# BreadBoard-Power-Supply_v10.net
KiCad netlist of a schematic drawn in EAGLE
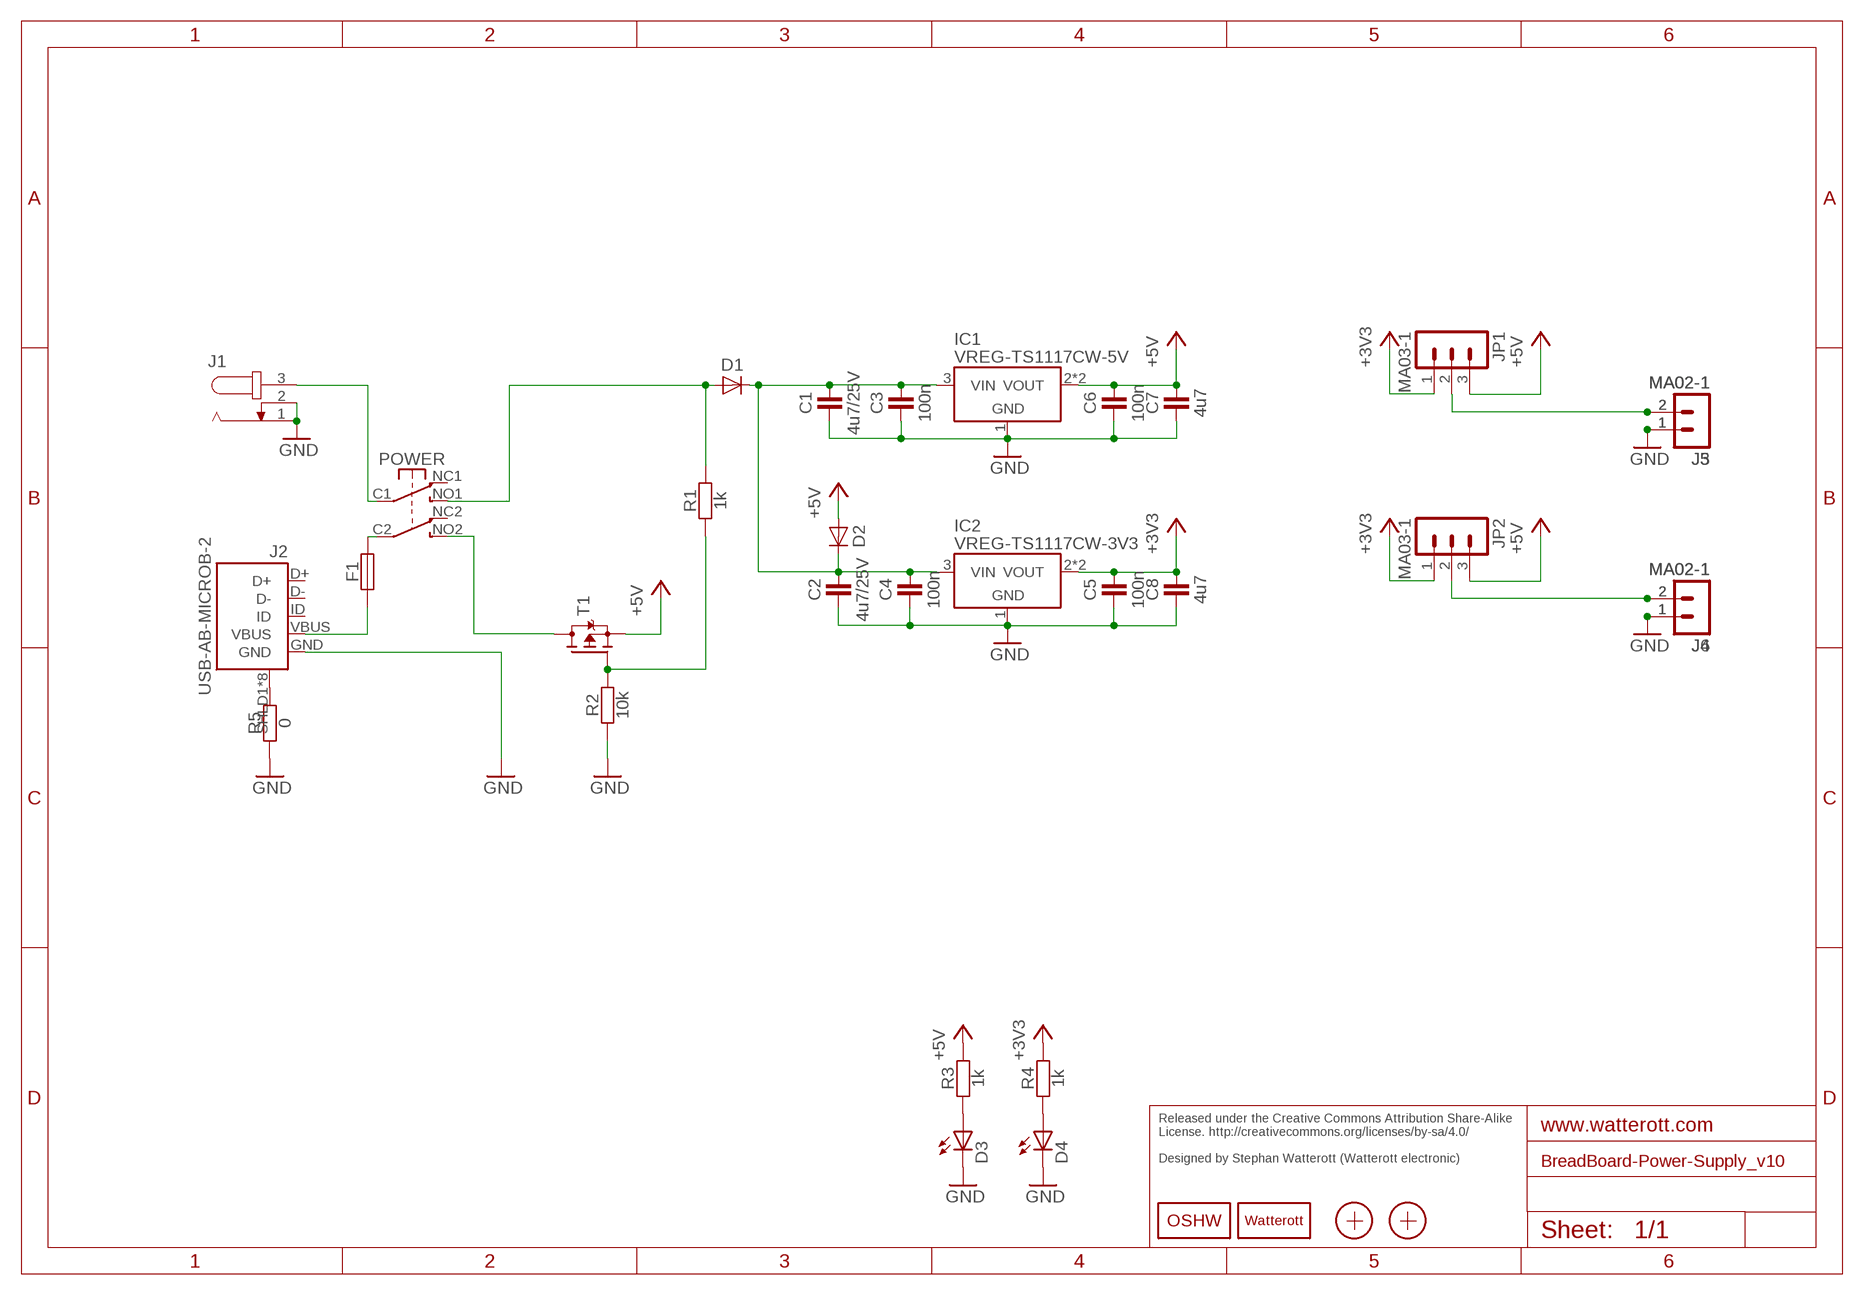
[diagram p0: schematic, sheet 1]

(export (version "E")
  (design (tool "Eeschema 10.0.6"))
  (components
    (comp (ref "C1")
      (value "4u7/25V")
      (footprint "eagle-import:C1206")
      (libsource (lib "eagle-import") (part "CAPACITOR-1206"))
    )
    (comp (ref "C2")
      (value "4u7/25V")
      (footprint "eagle-import:C1206")
      (libsource (lib "eagle-import") (part "CAPACITOR-1206"))
    )
    (comp (ref "C3")
      (value "100n")
      (footprint "eagle-import:C0402")
      (libsource (lib "eagle-import") (part "CAPACITOR-0402"))
    )
    (comp (ref "C4")
      (value "100n")
      (footprint "eagle-import:C0402")
      (libsource (lib "eagle-import") (part "CAPACITOR-0402"))
    )
    (comp (ref "C5")
      (value "100n")
      (footprint "eagle-import:C0402")
      (libsource (lib "eagle-import") (part "CAPACITOR-0402"))
    )
    (comp (ref "C6")
      (value "100n")
      (footprint "eagle-import:C0402")
      (libsource (lib "eagle-import") (part "CAPACITOR-0402"))
    )
    (comp (ref "C7")
      (value "4u7")
      (footprint "eagle-import:C0402")
      (libsource (lib "eagle-import") (part "CAPACITOR-0402"))
    )
    (comp (ref "C8")
      (value "4u7")
      (footprint "eagle-import:C0402")
      (libsource (lib "eagle-import") (part "CAPACITOR-0402"))
    )
    (comp (ref "D1")
      (value "DIODE-SOD80")
      (footprint "eagle-import:SOD80")
      (libsource (lib "eagle-import") (part "DIODE-SOD80"))
    )
    (comp (ref "D2")
      (value "DIODE-SOD80")
      (footprint "eagle-import:SOD80")
      (libsource (lib "eagle-import") (part "DIODE-SOD80"))
    )
    (comp (ref "D3")
      (value "LED-0603")
      (footprint "eagle-import:C0603")
      (libsource (lib "eagle-import") (part "LED-0603"))
    )
    (comp (ref "D4")
      (value "LED-0603")
      (footprint "eagle-import:C0603")
      (libsource (lib "eagle-import") (part "LED-0603"))
    )
    (comp (ref "F1")
      (value "FUSE-0805")
      (footprint "eagle-import:C0805")
      (libsource (lib "eagle-import") (part "FUSE-0805"))
    )
    (comp (ref "IC1")
      (value "VREG-TS1117CW-5V")
      (footprint "eagle-import:SOT223")
      (libsource (lib "eagle-import") (part "VREG-TS1117CW-5V"))
    )
    (comp (ref "IC2")
      (value "VREG-TS1117CW-3V3")
      (footprint "eagle-import:SOT223")
      (libsource (lib "eagle-import") (part "VREG-TS1117CW-3V3"))
    )
    (comp (ref "J1")
      (value "DC-JACK-2.1")
      (footprint "eagle-import:DC-JACK")
      (libsource (lib "eagle-import") (part "DC-JACK-2.1"))
    )
    (comp (ref "J2")
      (value "USB-AB-MICROB-2")
      (footprint "eagle-import:USB-MICROB-10118194")
      (libsource (lib "eagle-import") (part "USB-AB-MICROB-2"))
    )
    (comp (ref "J3")
      (value "MA02-1")
      (footprint "eagle-import:MA02-1")
      (libsource (lib "eagle-import") (part "MA02-1"))
    )
    (comp (ref "J4")
      (value "MA02-1")
      (footprint "eagle-import:MA02-1")
      (libsource (lib "eagle-import") (part "MA02-1"))
    )
    (comp (ref "J5")
      (value "MA02-1")
      (footprint "eagle-import:MA02-1")
      (libsource (lib "eagle-import") (part "MA02-1"))
    )
    (comp (ref "J6")
      (value "MA02-1")
      (footprint "eagle-import:MA02-1")
      (libsource (lib "eagle-import") (part "MA02-1"))
    )
    (comp (ref "JP1")
      (value "MA03-1")
      (footprint "eagle-import:MA03-1")
      (libsource (lib "eagle-import") (part "MA03-1"))
    )
    (comp (ref "JP2")
      (value "MA03-1")
      (footprint "eagle-import:MA03-1")
      (libsource (lib "eagle-import") (part "MA03-1"))
    )
    (comp (ref "LOGO1")
      (value "OSHW_LOGOX0070")
      (footprint "eagle-import:OSHW_6X70")
      (libsource (lib "eagle-import") (part "OSHW_LOGOX0070"))
    )
    (comp (ref "LOGO2")
      (value "LOGO-PLACE")
      (footprint "eagle-import:LOGO_TPLACE")
      (libsource (lib "eagle-import") (part "LOGO-PLACE"))
    )
    (comp (ref "POWER")
      (value "SW-2UMGF1260159")
      (footprint "eagle-import:GF1260159")
      (libsource (lib "eagle-import") (part "SW-2UMGF1260159"))
    )
    (comp (ref "R1")
      (value "1k")
      (footprint "eagle-import:C0402")
      (libsource (lib "eagle-import") (part "RESISTOR-0402"))
    )
    (comp (ref "R2")
      (value "10k")
      (footprint "eagle-import:C0402")
      (libsource (lib "eagle-import") (part "RESISTOR-0402"))
    )
    (comp (ref "R3")
      (value "1k")
      (footprint "eagle-import:C0402")
      (libsource (lib "eagle-import") (part "RESISTOR-0402"))
    )
    (comp (ref "R4")
      (value "1k")
      (footprint "eagle-import:C0402")
      (libsource (lib "eagle-import") (part "RESISTOR-0402"))
    )
    (comp (ref "R5")
      (value "0")
      (footprint "eagle-import:C0402")
      (libsource (lib "eagle-import") (part "RESISTOR-0402"))
    )
    (comp (ref "T1")
      (value "MOSFET-P-SOT23")
      (footprint "eagle-import:SOT23")
      (libsource (lib "eagle-import") (part "MOSFET-P-SOT23"))
    )
    (comp (ref "X1")
      (value "PASSER-07")
      (footprint "eagle-import:PASSER_07MM")
      (libsource (lib "eagle-import") (part "PASSER-07"))
    )
    (comp (ref "X2")
      (value "PASSER-07")
      (footprint "eagle-import:PASSER_07MM")
      (libsource (lib "eagle-import") (part "PASSER-07"))
    )
  )
  (nets
    (net (code "1") (name "+3V3") (class "Default")
      (node (ref "C5") (pin "2") (pinfunction "2_2") (pintype "passive"))
      (node (ref "C8") (pin "2") (pinfunction "2_2") (pintype "passive"))
      (node (ref "IC2") (pin "2") (pinfunction "VOUT_2") (pintype "power_in"))
      (node (ref "IC2") (pin "4") (pinfunction "VOUT_4") (pintype "power_in"))
      (node (ref "JP1") (pin "1") (pinfunction "1_1") (pintype "passive"))
      (node (ref "JP2") (pin "1") (pinfunction "1_1") (pintype "passive"))
      (node (ref "R4") (pin "2") (pinfunction "2_2") (pintype "passive"))
    )
    (net (code "2") (name "+5V") (class "Default")
      (node (ref "C6") (pin "2") (pinfunction "2_2") (pintype "passive"))
      (node (ref "C7") (pin "2") (pinfunction "2_2") (pintype "passive"))
      (node (ref "D2") (pin "A") (pinfunction "A_A") (pintype "passive"))
      (node (ref "IC1") (pin "2") (pinfunction "VOUT_2") (pintype "power_in"))
      (node (ref "IC1") (pin "4") (pinfunction "VOUT_4") (pintype "power_in"))
      (node (ref "JP1") (pin "3") (pinfunction "3_3") (pintype "passive"))
      (node (ref "JP2") (pin "3") (pinfunction "3_3") (pintype "passive"))
      (node (ref "R3") (pin "2") (pinfunction "2_2") (pintype "passive"))
      (node (ref "T1") (pin "2") (pinfunction "S_2") (pintype "passive"))
    )
    (net (code "3") (name "GND") (class "Default")
      (node (ref "C1") (pin "1") (pinfunction "1_1") (pintype "passive"))
      (node (ref "C2") (pin "1") (pinfunction "1_1") (pintype "passive"))
      (node (ref "C3") (pin "1") (pinfunction "1_1") (pintype "passive"))
      (node (ref "C4") (pin "1") (pinfunction "1_1") (pintype "passive"))
      (node (ref "C5") (pin "1") (pinfunction "1_1") (pintype "passive"))
      (node (ref "C6") (pin "1") (pinfunction "1_1") (pintype "passive"))
      (node (ref "C7") (pin "1") (pinfunction "1_1") (pintype "passive"))
      (node (ref "C8") (pin "1") (pinfunction "1_1") (pintype "passive"))
      (node (ref "D3") (pin "C") (pinfunction "C_C") (pintype "passive"))
      (node (ref "D4") (pin "C") (pinfunction "C_C") (pintype "passive"))
      (node (ref "IC1") (pin "1") (pinfunction "GND_1") (pintype "power_in"))
      (node (ref "IC2") (pin "1") (pinfunction "GND_1") (pintype "power_in"))
      (node (ref "J1") (pin "1") (pinfunction "1_1") (pintype "passive"))
      (node (ref "J1") (pin "2") (pinfunction "2_2") (pintype "passive"))
      (node (ref "J2") (pin "GND") (pinfunction "GND_GND") (pintype "power_in"))
      (node (ref "J3") (pin "1") (pinfunction "1_1") (pintype "passive"))
      (node (ref "J4") (pin "1") (pinfunction "1_1") (pintype "passive"))
      (node (ref "J5") (pin "1") (pinfunction "1_1") (pintype "passive"))
      (node (ref "J6") (pin "1") (pinfunction "1_1") (pintype "passive"))
      (node (ref "R2") (pin "1") (pinfunction "1_1") (pintype "passive"))
      (node (ref "R5") (pin "1") (pinfunction "1_1") (pintype "passive"))
    )
    (net (code "4") (name "Net-(D3-PadA)") (class "Default")
      (node (ref "D3") (pin "A") (pinfunction "A_A") (pintype "passive"))
      (node (ref "R3") (pin "1") (pinfunction "1_1") (pintype "passive"))
    )
    (net (code "5") (name "Net-(D4-PadA)") (class "Default")
      (node (ref "D4") (pin "A") (pinfunction "A_A") (pintype "passive"))
      (node (ref "R4") (pin "1") (pinfunction "1_1") (pintype "passive"))
    )
    (net (code "6") (name "Net-(F1-Pad1)") (class "Default")
      (node (ref "F1") (pin "1") (pinfunction "1_1") (pintype "passive"))
      (node (ref "J2") (pin "VBUS") (pinfunction "VBUS_VBUS") (pintype "power_in"))
    )
    (net (code "7") (name "Net-(IC1-VIN)") (class "Default")
      (node (ref "C1") (pin "2") (pinfunction "2_2") (pintype "passive"))
      (node (ref "C2") (pin "2") (pinfunction "2_2") (pintype "passive"))
      (node (ref "C3") (pin "2") (pinfunction "2_2") (pintype "passive"))
      (node (ref "C4") (pin "2") (pinfunction "2_2") (pintype "passive"))
      (node (ref "D1") (pin "C") (pinfunction "C_C") (pintype "passive"))
      (node (ref "D2") (pin "C") (pinfunction "C_C") (pintype "passive"))
      (node (ref "IC1") (pin "3") (pinfunction "VIN_3") (pintype "power_in"))
      (node (ref "IC2") (pin "3") (pinfunction "VIN_3") (pintype "power_in"))
    )
    (net (code "8") (name "Net-(J2-SHIELD-PadSHLD1)") (class "Default")
      (node (ref "J2") (pin "SHLD1") (pinfunction "SHIELD_SHLD1") (pintype "passive"))
      (node (ref "J2") (pin "SHLD2") (pinfunction "SHIELD_SHLD2") (pintype "passive"))
      (node (ref "J2") (pin "SHLD3") (pinfunction "SHIELD_SHLD3") (pintype "passive"))
      (node (ref "J2") (pin "SHLD4") (pinfunction "SHIELD_SHLD4") (pintype "passive"))
      (node (ref "J2") (pin "SHLD5") (pinfunction "SHIELD_SHLD5") (pintype "passive"))
      (node (ref "J2") (pin "SHLD6") (pinfunction "SHIELD_SHLD6") (pintype "passive"))
      (node (ref "J2") (pin "SHLD7") (pinfunction "SHIELD_SHLD7") (pintype "passive"))
      (node (ref "J2") (pin "SHLD8") (pinfunction "SHIELD_SHLD8") (pintype "passive"))
      (node (ref "R5") (pin "2") (pinfunction "2_2") (pintype "passive"))
    )
    (net (code "9") (name "Net-(J3-Pad2)") (class "Default")
      (node (ref "J3") (pin "2") (pinfunction "2_2") (pintype "passive"))
      (node (ref "J5") (pin "2") (pinfunction "2_2") (pintype "passive"))
      (node (ref "JP1") (pin "2") (pinfunction "2_2") (pintype "passive"))
    )
    (net (code "10") (name "Net-(J4-Pad2)") (class "Default")
      (node (ref "J4") (pin "2") (pinfunction "2_2") (pintype "passive"))
      (node (ref "J6") (pin "2") (pinfunction "2_2") (pintype "passive"))
      (node (ref "JP2") (pin "2") (pinfunction "2_2") (pintype "passive"))
    )
    (net (code "11") (name "Net-(POWER-P1)") (class "Default")
      (node (ref "J1") (pin "3") (pinfunction "3_3") (pintype "passive"))
      (node (ref "POWER") (pin "C1") (pinfunction "P1_C1") (pintype "passive"))
    )
    (net (code "12") (name "Net-(POWER-P2)") (class "Default")
      (node (ref "F1") (pin "2") (pinfunction "2_2") (pintype "passive"))
      (node (ref "POWER") (pin "C2") (pinfunction "P2_C2") (pintype "passive"))
    )
    (net (code "13") (name "Net-(POWER-S1)") (class "Default")
      (node (ref "D1") (pin "A") (pinfunction "A_A") (pintype "passive"))
      (node (ref "POWER") (pin "NO1") (pinfunction "S1_NO1") (pintype "passive"))
      (node (ref "R1") (pin "2") (pinfunction "2_2") (pintype "passive"))
    )
    (net (code "14") (name "Net-(POWER-S2)") (class "Default")
      (node (ref "POWER") (pin "NO2") (pinfunction "S2_NO2") (pintype "passive"))
      (node (ref "T1") (pin "3") (pinfunction "D_3") (pintype "passive"))
    )
    (net (code "15") (name "Net-(T1-G)") (class "Default")
      (node (ref "R1") (pin "1") (pinfunction "1_1") (pintype "passive"))
      (node (ref "R2") (pin "2") (pinfunction "2_2") (pintype "passive"))
      (node (ref "T1") (pin "1") (pinfunction "G_1") (pintype "passive"))
    )
    (net (code "16") (name "unconnected-(J2-PadD+)") (class "Default")
      (node (ref "J2") (pin "D+") (pinfunction "D+_D+") (pintype "bidirectional"))
    )
    (net (code "17") (name "unconnected-(J2-PadD-)") (class "Default")
      (node (ref "J2") (pin "D-") (pinfunction "D-_D-") (pintype "bidirectional"))
    )
    (net (code "18") (name "unconnected-(J2-PadID)") (class "Default")
      (node (ref "J2") (pin "ID") (pinfunction "ID_ID") (pintype "bidirectional"))
    )
    (net (code "19") (name "unconnected-(POWER-O1-PadNC1)") (class "Default")
      (node (ref "POWER") (pin "NC1") (pinfunction "O1_NC1") (pintype "passive"))
    )
    (net (code "20") (name "unconnected-(POWER-O2-PadNC2)") (class "Default")
      (node (ref "POWER") (pin "NC2") (pinfunction "O2_NC2") (pintype "passive"))
    )
  )
)
